# m913-dev-adapter.net
KiCad netlist of a schematic drawn in EAGLE
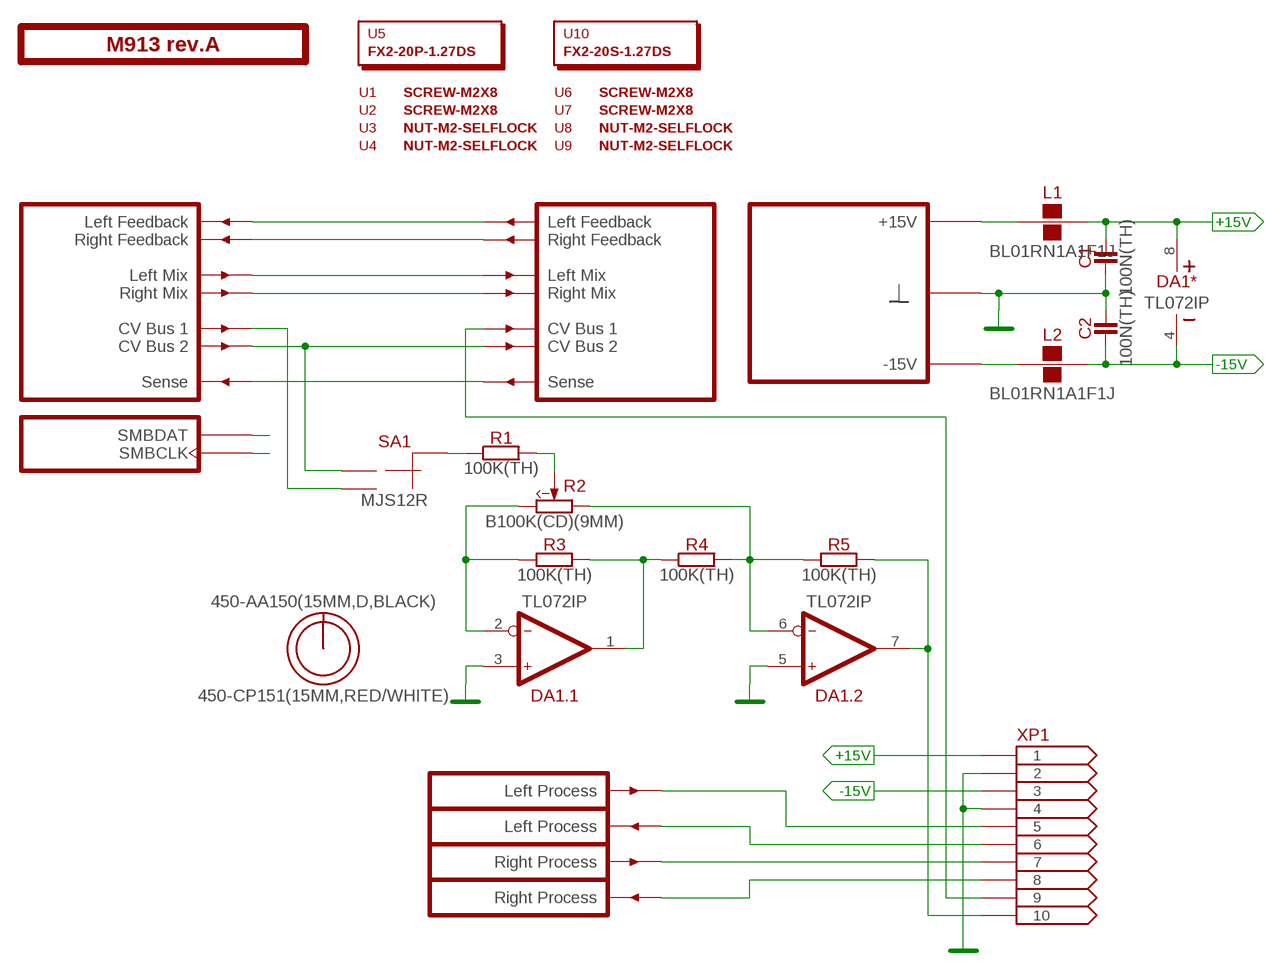
[diagram p0: schematic, sheet 1]

(export (version "E")
  (design (tool "Eeschema 10.0.6"))
  (components
    (comp (ref "C1")
      (value "100N(TH)")
      (footprint "eagle-import:C050-024X044")
      (libsource (lib "eagle-import") (part "?100N(TH)"))
    )
    (comp (ref "C2")
      (value "100N(TH)")
      (footprint "eagle-import:C050-024X044")
      (libsource (lib "eagle-import") (part "?100N(TH)"))
    )
    (comp (ref "DA1")
      (value "TL072IP")
      (footprint "eagle-import:DIP-8")
      (libsource (lib "eagle-import") (part "TL072IP"))
    )
    (comp (ref "L1")
      (value "BL01RN1A1F1J")
      (footprint "eagle-import:BL01RN1A")
      (libsource (lib "eagle-import") (part "BL01RN1A?1F1J"))
    )
    (comp (ref "L2")
      (value "BL01RN1A1F1J")
      (footprint "eagle-import:BL01RN1A")
      (libsource (lib "eagle-import") (part "BL01RN1A?1F1J"))
    )
    (comp (ref "O1")
      (value "450-AA150(15MM,D,BLACK)")
      (footprint "eagle-import:EMPTY")
      (libsource (lib "eagle-import") (part "450-AA?150(15MM,D,BLACK)"))
    )
    (comp (ref "O2")
      (value "450-CP151(15MM,RED/WHITE)")
      (footprint "eagle-import:EMPTY")
      (libsource (lib "eagle-import") (part "450-C?P151(15MM,RED/WHITE)"))
    )
    (comp (ref "PCB1")
      (value "M913 rev.A")
      (footprint "eagle-import:ST2-BOARD-26")
      (libsource (lib "eagle-import") (part "ST2-BOARD-?26"))
    )
    (comp (ref "R1")
      (value "100K(TH)")
      (footprint "eagle-import:R-0207_10")
      (libsource (lib "eagle-import") (part "?100K(TH)"))
    )
    (comp (ref "R2")
      (value "B100K(CD)(9MM)")
      (footprint "eagle-import:RV09-SINGLE")
      (libsource (lib "eagle-import") (part "?B100K(CD)(9MM)"))
    )
    (comp (ref "R3")
      (value "100K(TH)")
      (footprint "eagle-import:R-0207_10")
      (libsource (lib "eagle-import") (part "?100K(TH)"))
    )
    (comp (ref "R4")
      (value "100K(TH)")
      (footprint "eagle-import:R-0207_10")
      (libsource (lib "eagle-import") (part "?100K(TH)"))
    )
    (comp (ref "R5")
      (value "100K(TH)")
      (footprint "eagle-import:R-0207_10")
      (libsource (lib "eagle-import") (part "?100K(TH)"))
    )
    (comp (ref "SA1")
      (value "MJS12R")
      (footprint "eagle-import:APEM-MJS12R")
      (libsource (lib "eagle-import") (part "MJS12R"))
    )
    (comp (ref "U1")
      (value "SCREW-M2X8")
      (footprint "eagle-import:EMPTY")
      (libsource (lib "eagle-import") (part "?SCREW-M2X8"))
    )
    (comp (ref "U2")
      (value "SCREW-M2X8")
      (footprint "eagle-import:EMPTY")
      (libsource (lib "eagle-import") (part "?SCREW-M2X8"))
    )
    (comp (ref "U3")
      (value "NUT-M2-SELFLOCK")
      (footprint "eagle-import:EMPTY")
      (libsource (lib "eagle-import") (part "?NUT-M2-SELFLOCK"))
    )
    (comp (ref "U4")
      (value "NUT-M2-SELFLOCK")
      (footprint "eagle-import:EMPTY")
      (libsource (lib "eagle-import") (part "?NUT-M2-SELFLOCK"))
    )
    (comp (ref "U5")
      (value "FX2-20P-1.27DS")
      (footprint "eagle-import:EMPTY")
      (libsource (lib "eagle-import") (part "?FX2-20P-1.27DS"))
    )
    (comp (ref "U6")
      (value "SCREW-M2X8")
      (footprint "eagle-import:EMPTY")
      (libsource (lib "eagle-import") (part "?SCREW-M2X8"))
    )
    (comp (ref "U7")
      (value "SCREW-M2X8")
      (footprint "eagle-import:EMPTY")
      (libsource (lib "eagle-import") (part "?SCREW-M2X8"))
    )
    (comp (ref "U8")
      (value "NUT-M2-SELFLOCK")
      (footprint "eagle-import:EMPTY")
      (libsource (lib "eagle-import") (part "?NUT-M2-SELFLOCK"))
    )
    (comp (ref "U9")
      (value "NUT-M2-SELFLOCK")
      (footprint "eagle-import:EMPTY")
      (libsource (lib "eagle-import") (part "?NUT-M2-SELFLOCK"))
    )
    (comp (ref "U10")
      (value "FX2-20S-1.27DS")
      (footprint "eagle-import:EMPTY")
      (libsource (lib "eagle-import") (part "?FX2-20S-1.27DS"))
    )
    (comp (ref "XP1")
      (value "CONN-10-IDC")
      (footprint "eagle-import:ML10")
      (libsource (lib "eagle-import") (part "CONN-10-?IDC"))
    )
  )
  (nets
    (net (code "1") (name "+15V") (class "Default")
      (node (ref "C1") (pin "2") (pinfunction "2_2") (pintype "passive"))
      (node (ref "DA1") (pin "8") (pinfunction "V+_8") (pintype "power_in"))
      (node (ref "L1") (pin "2") (pinfunction "2_2") (pintype "passive"))
      (node (ref "XP1") (pin "1") (pinfunction "1_1") (pintype "passive"))
    )
    (net (code "2") (name "-15V") (class "Default")
      (node (ref "C2") (pin "1") (pinfunction "1_1") (pintype "passive"))
      (node (ref "DA1") (pin "4") (pinfunction "V-_4") (pintype "power_in"))
      (node (ref "L2") (pin "2") (pinfunction "2_2") (pintype "passive"))
      (node (ref "XP1") (pin "3") (pinfunction "3_3") (pintype "passive"))
    )
    (net (code "3") (name "GND") (class "Default")
      (node (ref "C1") (pin "1") (pinfunction "1_1") (pintype "passive"))
      (node (ref "C2") (pin "2") (pinfunction "2_2") (pintype "passive"))
      (node (ref "DA1") (pin "3") (pinfunction "IN+_3") (pintype "input"))
      (node (ref "DA1") (pin "5") (pinfunction "IN+_5") (pintype "input"))
      (node (ref "PCB1") (pin "B4") (pinfunction "GND_B4") (pintype "bidirectional"))
      (node (ref "PCB1") (pin "B4'") (pinfunction "GND_B4'") (pintype "bidirectional"))
      (node (ref "PCB1") (pin "B5") (pinfunction "GND_B5") (pintype "bidirectional"))
      (node (ref "PCB1") (pin "B5'") (pinfunction "GND_B5'") (pintype "bidirectional"))
      (node (ref "PCB1") (pin "B6") (pinfunction "GND_B6") (pintype "bidirectional"))
      (node (ref "PCB1") (pin "B6'") (pinfunction "GND_B6'") (pintype "bidirectional"))
      (node (ref "PCB1") (pin "B7") (pinfunction "GND_B7") (pintype "bidirectional"))
      (node (ref "PCB1") (pin "B7'") (pinfunction "GND_B7'") (pintype "bidirectional"))
      (node (ref "PCB1") (pin "B8") (pinfunction "GND_B8") (pintype "bidirectional"))
      (node (ref "PCB1") (pin "B8'") (pinfunction "GND_B8'") (pintype "bidirectional"))
      (node (ref "XP1") (pin "2") (pinfunction "2_2") (pintype "passive"))
      (node (ref "XP1") (pin "4") (pinfunction "4_4") (pintype "passive"))
    )
    (net (code "4") (name "Net-(DA1B-IN-)") (class "Default")
      (node (ref "DA1") (pin "2") (pinfunction "IN-_2") (pintype "input"))
      (node (ref "R2") (pin "3") (pinfunction "CW_3") (pintype "passive"))
      (node (ref "R3") (pin "1") (pinfunction "1_1") (pintype "passive"))
    )
    (net (code "5") (name "Net-(DA1B-OUT)") (class "Default")
      (node (ref "DA1") (pin "1") (pinfunction "OUT_1") (pintype "output"))
      (node (ref "R3") (pin "2") (pinfunction "2_2") (pintype "passive"))
      (node (ref "R4") (pin "1") (pinfunction "1_1") (pintype "passive"))
    )
    (net (code "6") (name "Net-(DA1C-IN-)") (class "Default")
      (node (ref "DA1") (pin "6") (pinfunction "IN-_6") (pintype "input"))
      (node (ref "R2") (pin "1") (pinfunction "CCW_1") (pintype "passive"))
      (node (ref "R4") (pin "2") (pinfunction "2_2") (pintype "passive"))
      (node (ref "R5") (pin "1") (pinfunction "1_1") (pintype "passive"))
    )
    (net (code "7") (name "Net-(DA1C-OUT)") (class "Default")
      (node (ref "DA1") (pin "7") (pinfunction "OUT_7") (pintype "output"))
      (node (ref "R5") (pin "2") (pinfunction "2_2") (pintype "passive"))
      (node (ref "XP1") (pin "10") (pinfunction "10_10") (pintype "passive"))
    )
    (net (code "8") (name "Net-(L1-Pad1)") (class "Default")
      (node (ref "L1") (pin "1") (pinfunction "1_1") (pintype "passive"))
      (node (ref "PCB1") (pin "A+15") (pinfunction "P+15V_A+15") (pintype "bidirectional"))
      (node (ref "PCB1") (pin "A+15'") (pinfunction "P+15V_A+15'") (pintype "bidirectional"))
      (node (ref "PCB1") (pin "B+15") (pinfunction "P+15V_B+15") (pintype "bidirectional"))
      (node (ref "PCB1") (pin "B+15'") (pinfunction "P+15V_B+15'") (pintype "bidirectional"))
    )
    (net (code "9") (name "Net-(L2-Pad1)") (class "Default")
      (node (ref "L2") (pin "1") (pinfunction "1_1") (pintype "passive"))
      (node (ref "PCB1") (pin "A-15") (pinfunction "P-15V_A-15") (pintype "bidirectional"))
      (node (ref "PCB1") (pin "A-15'") (pinfunction "P-15V_A-15'") (pintype "bidirectional"))
      (node (ref "PCB1") (pin "B-15") (pinfunction "P-15V_B-15") (pintype "bidirectional"))
      (node (ref "PCB1") (pin "B-15'") (pinfunction "P-15V_B-15'") (pintype "bidirectional"))
    )
    (net (code "10") (name "Net-(PCB1B-INL)") (class "Default")
      (node (ref "PCB1") (pin "BINL") (pinfunction "INL_BINL") (pintype "bidirectional"))
      (node (ref "XP1") (pin "5") (pinfunction "5_5") (pintype "passive"))
    )
    (net (code "11") (name "Net-(PCB1C-INR)") (class "Default")
      (node (ref "PCB1") (pin "BINR") (pinfunction "INR_BINR") (pintype "bidirectional"))
      (node (ref "XP1") (pin "7") (pinfunction "7_7") (pintype "passive"))
    )
    (net (code "12") (name "Net-(PCB1D-OUTL)") (class "Default")
      (node (ref "PCB1") (pin "BOUTL'") (pinfunction "OUTL_BOUTL'") (pintype "bidirectional"))
      (node (ref "XP1") (pin "6") (pinfunction "6_6") (pintype "passive"))
    )
    (net (code "13") (name "Net-(PCB1E-OUTR)") (class "Default")
      (node (ref "PCB1") (pin "BOUTR'") (pinfunction "OUTR_BOUTR'") (pintype "bidirectional"))
      (node (ref "XP1") (pin "8") (pinfunction "8_8") (pintype "passive"))
    )
    (net (code "14") (name "Net-(PCB1F-CV1)") (class "Default")
      (node (ref "PCB1") (pin "ACV1") (pinfunction "CV1_ACV1") (pintype "bidirectional"))
      (node (ref "SA1") (pin "NO") (pinfunction "2_NO") (pintype "passive"))
    )
    (net (code "15") (name "Net-(PCB1F-CV2)") (class "Default")
      (node (ref "PCB1") (pin "ACV2") (pinfunction "CV2_ACV2") (pintype "bidirectional"))
      (node (ref "PCB1") (pin "ACV2'") (pinfunction "CV2'_ACV2'") (pintype "bidirectional"))
      (node (ref "SA1") (pin "NC") (pinfunction "1_NC") (pintype "passive"))
    )
    (net (code "16") (name "Net-(PCB1F-LFBK)") (class "Default")
      (node (ref "PCB1") (pin "ALFBK") (pinfunction "LFBK_ALFBK") (pintype "bidirectional"))
      (node (ref "PCB1") (pin "ALFBK'") (pinfunction "LFBK'_ALFBK'") (pintype "bidirectional"))
    )
    (net (code "17") (name "Net-(PCB1F-LMIX)") (class "Default")
      (node (ref "PCB1") (pin "ALMIX") (pinfunction "LMIX_ALMIX") (pintype "bidirectional"))
      (node (ref "PCB1") (pin "ALMIX'") (pinfunction "LMIX'_ALMIX'") (pintype "bidirectional"))
    )
    (net (code "18") (name "Net-(PCB1F-RFBK)") (class "Default")
      (node (ref "PCB1") (pin "ARFBK") (pinfunction "RFBK_ARFBK") (pintype "bidirectional"))
      (node (ref "PCB1") (pin "ARFBK'") (pinfunction "RFBK'_ARFBK'") (pintype "bidirectional"))
    )
    (net (code "19") (name "Net-(PCB1F-RMIX)") (class "Default")
      (node (ref "PCB1") (pin "ARMIX") (pinfunction "RMIX_ARMIX") (pintype "bidirectional"))
      (node (ref "PCB1") (pin "ARMIX'") (pinfunction "RMIX'_ARMIX'") (pintype "bidirectional"))
    )
    (net (code "20") (name "Net-(PCB1F-SENSE)") (class "Default")
      (node (ref "PCB1") (pin "BSENSE") (pinfunction "SENSE_BSENSE") (pintype "bidirectional"))
      (node (ref "PCB1") (pin "BSENSE'") (pinfunction "SENSE'_BSENSE'") (pintype "bidirectional"))
    )
    (net (code "21") (name "Net-(PCB1G-CV1')") (class "Default")
      (node (ref "PCB1") (pin "ACV1'") (pinfunction "CV1'_ACV1'") (pintype "bidirectional"))
      (node (ref "XP1") (pin "9") (pinfunction "9_9") (pintype "passive"))
    )
    (net (code "22") (name "Net-(PCB1H-SMBCLK-PadASMBCLK')") (class "Default")
      (node (ref "PCB1") (pin "ASMBCLK") (pinfunction "SMBCLK_ASMBCLK") (pintype "bidirectional"))
      (node (ref "PCB1") (pin "ASMBCLK'") (pinfunction "SMBCLK_ASMBCLK'") (pintype "bidirectional"))
    )
    (net (code "23") (name "Net-(PCB1H-SMBDAT-PadASMBDAT')") (class "Default")
      (node (ref "PCB1") (pin "ASMBDAT") (pinfunction "SMBDAT_ASMBDAT") (pintype "bidirectional"))
      (node (ref "PCB1") (pin "ASMBDAT'") (pinfunction "SMBDAT_ASMBDAT'") (pintype "bidirectional"))
    )
    (net (code "24") (name "Net-(R2-W)") (class "Default")
      (node (ref "R1") (pin "2") (pinfunction "2_2") (pintype "passive"))
      (node (ref "R2") (pin "2") (pinfunction "W_2") (pintype "passive"))
    )
    (net (code "25") (name "Net-(SA1-CM)") (class "Default")
      (node (ref "R1") (pin "1") (pinfunction "1_1") (pintype "passive"))
      (node (ref "SA1") (pin "C") (pinfunction "CM_C") (pintype "passive"))
    )
  )
)
